# delay_channel.net
KiCad netlist of a schematic drawn in Altium Designer
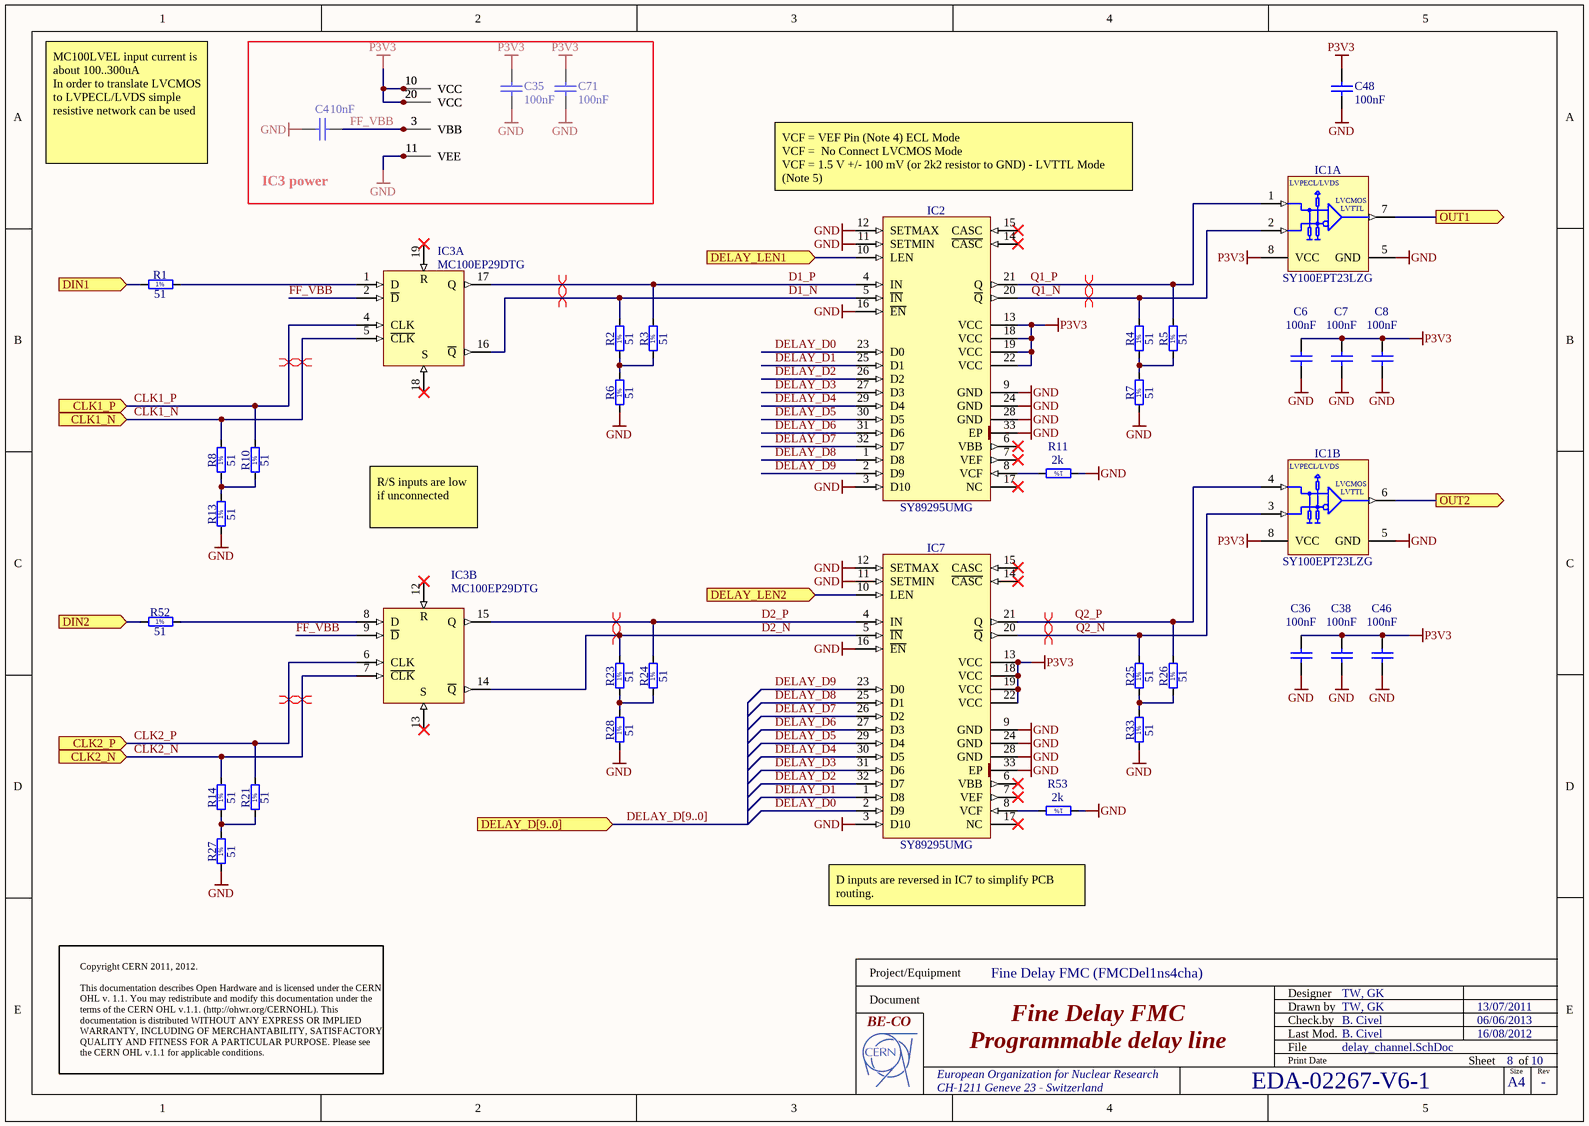
[diagram p0: delay_channel.SchDoc]

(export (version "E")
  (design (tool "Eeschema 10.0.6"))
  (components
    (comp (ref "C4")
      (value "10nF")
      (footprint "CAPC1608X87N")
      (description "Non-polarised capacitor")
      (fields
        (field (name "PART NUMBER") "CC0603_10NF_50V_10%_X7R")
        (field (name "VOLTAGE") "50V")
        (field (name "AUTHOR") "CERN DEM JLC")
      )
      (libsource (lib "Capacitors") (part "Capacitor - non polarized"))
    )
    (comp (ref "C6")
      (value "100nF")
      (footprint "CAPC1608X87N")
      (description "Non-polarised capacitor")
      (fields
        (field (name "MANUFACTURER1 PART NUMBER") "223858615649")
        (field (name "MANUFACTURER") "GENERIC")
        (field (name "AUTHOR") "CERN DEM JLC")
      )
      (libsource (lib "Capacitors") (part "Capacitor - non polarized"))
    )
    (comp (ref "C7")
      (value "100nF")
      (footprint "CAPC1608X87N")
      (description "Non-polarised capacitor")
      (fields
        (field (name "MANUFACTURER1 PART NUMBER") "223858615649")
        (field (name "MANUFACTURER") "GENERIC")
        (field (name "AUTHOR") "CERN DEM JLC")
      )
      (libsource (lib "Capacitors") (part "Capacitor - non polarized"))
    )
    (comp (ref "C8")
      (value "100nF")
      (footprint "CAPC1608X87N")
      (description "Non-polarised capacitor")
      (fields
        (field (name "MANUFACTURER1 PART NUMBER") "223858615649")
        (field (name "MANUFACTURER") "GENERIC")
        (field (name "AUTHOR") "CERN DEM JLC")
      )
      (libsource (lib "Capacitors") (part "Capacitor - non polarized"))
    )
    (comp (ref "C35")
      (value "100nF")
      (footprint "CAPC1608X87N")
      (description "Non-polarised capacitor")
      (fields
        (field (name "MANUFACTURER1 PART NUMBER") "223858615649")
        (field (name "MANUFACTURER") "GENERIC")
        (field (name "AUTHOR") "CERN DEM JLC")
      )
      (libsource (lib "Capacitors") (part "Capacitor - non polarized"))
    )
    (comp (ref "C36")
      (value "100nF")
      (footprint "CAPC1608X87N")
      (description "Non-polarised capacitor")
      (fields
        (field (name "MANUFACTURER1 PART NUMBER") "223858615649")
        (field (name "MANUFACTURER") "GENERIC")
        (field (name "AUTHOR") "CERN DEM JLC")
      )
      (libsource (lib "Capacitors") (part "Capacitor - non polarized"))
    )
    (comp (ref "C38")
      (value "100nF")
      (footprint "CAPC1608X87N")
      (description "Non-polarised capacitor")
      (fields
        (field (name "MANUFACTURER1 PART NUMBER") "223858615649")
        (field (name "MANUFACTURER") "GENERIC")
        (field (name "AUTHOR") "CERN DEM JLC")
      )
      (libsource (lib "Capacitors") (part "Capacitor - non polarized"))
    )
    (comp (ref "C46")
      (value "100nF")
      (footprint "CAPC1608X87N")
      (description "Non-polarised capacitor")
      (fields
        (field (name "MANUFACTURER1 PART NUMBER") "223858615649")
        (field (name "MANUFACTURER") "GENERIC")
        (field (name "AUTHOR") "CERN DEM JLC")
      )
      (libsource (lib "Capacitors") (part "Capacitor - non polarized"))
    )
    (comp (ref "C48")
      (value "100nF")
      (footprint "CAPC1608X87N")
      (description "Non-polarised capacitor")
      (fields
        (field (name "MANUFACTURER1 PART NUMBER") "223858615649")
        (field (name "MANUFACTURER") "GENERIC")
        (field (name "AUTHOR") "CERN DEM JLC")
      )
      (libsource (lib "Capacitors") (part "Capacitor - non polarized"))
    )
    (comp (ref "C71")
      (value "100nF")
      (footprint "CAPC1608X87N")
      (description "Non-polarised capacitor")
      (fields
        (field (name "MANUFACTURER1 PART NUMBER") "223858615649")
        (field (name "MANUFACTURER") "GENERIC")
        (field (name "AUTHOR") "CERN DEM JLC")
      )
      (libsource (lib "Capacitors") (part "Capacitor - non polarized"))
    )
    (comp (ref "IC1")
      (value "SY100EPT23LZG")
      (footprint "SOIC127P600X175-8N")
      (description "3.3V Dual Differential LVPECL/LVDS/CML  to LVTTL/LVCMOS Translator")
      (fields (field (name "MANUFACTURER") "MICREL") (field (name "AUTHOR") "CERN DEM JLC"))
      (libsource (lib "ICs And Semiconductors") (part "100EPT23D_a"))
    )
    (comp (ref "IC2")
      (value "SY89295UMG")
      (footprint "QFN50P500X500X90-33N-S320")
      (description "2.5V/3.3V 1.5GHz Precision LVPECL Programmable Delay")
      (fields (field (name "MANUFACTURER") "MICREL") (field (name "AUTHOR") "CERN DEM JLC"))
      (libsource (lib "ICs And Semiconductors") (part "SY89295UMG"))
    )
    (comp (ref "IC3")
      (value "MC100EP29DTG")
      (footprint "SOP65P640X120-20N")
      (description "3.3V/5V ECL Dual Differential Data and Clock D Flip-Flop With Set and Reset")
      (fields (field (name "MANUFACTURER") "ON SEMICONDUCTOR") (field (name "AUTHOR") "CERN DEM JLC"))
      (libsource (lib "ICs And Semiconductors") (part "100EP29D"))
    )
    (comp (ref "IC7")
      (value "SY89295UMG")
      (footprint "QFN50P500X500X90-33N-S320")
      (description "2.5V/3.3V 1.5GHz Precision LVPECL Programmable Delay")
      (fields (field (name "MANUFACTURER") "MICREL") (field (name "AUTHOR") "CERN DEM JLC"))
      (libsource (lib "ICs And Semiconductors") (part "SY89295UMG"))
    )
    (comp (ref "R1")
      (value "51")
      (footprint "RESC1608X55N")
      (description "Resistor - 1%")
      (fields
        (field (name "PART NUMBER") "R0603_51R_1%_0.1W_100PPM")
        (field (name "POWER") "0.1W")
        (field (name "AUTHOR") "CERN DEM JLC")
      )
      (libsource (lib "Resistors") (part "Resistor - 1%"))
    )
    (comp (ref "R2")
      (value "51")
      (footprint "RESC1608X55N")
      (description "Resistor - 1%")
      (fields
        (field (name "PART NUMBER") "R0603_51R_1%_0.1W_100PPM")
        (field (name "POWER") "0.1W")
        (field (name "AUTHOR") "CERN DEM JLC")
      )
      (libsource (lib "Resistors") (part "Resistor - 1%"))
    )
    (comp (ref "R3")
      (value "51")
      (footprint "RESC1608X55N")
      (description "Resistor - 1%")
      (fields
        (field (name "PART NUMBER") "R0603_51R_1%_0.1W_100PPM")
        (field (name "POWER") "0.1W")
        (field (name "AUTHOR") "CERN DEM JLC")
      )
      (libsource (lib "Resistors") (part "Resistor - 1%"))
    )
    (comp (ref "R4")
      (value "51")
      (footprint "RESC1608X55N")
      (description "Resistor - 1%")
      (fields
        (field (name "PART NUMBER") "R0603_51R_1%_0.1W_100PPM")
        (field (name "POWER") "0.1W")
        (field (name "AUTHOR") "CERN DEM JLC")
      )
      (libsource (lib "Resistors") (part "Resistor - 1%"))
    )
    (comp (ref "R5")
      (value "51")
      (footprint "RESC1608X55N")
      (description "Resistor - 1%")
      (fields
        (field (name "PART NUMBER") "R0603_51R_1%_0.1W_100PPM")
        (field (name "POWER") "0.1W")
        (field (name "AUTHOR") "CERN DEM JLC")
      )
      (libsource (lib "Resistors") (part "Resistor - 1%"))
    )
    (comp (ref "R6")
      (value "51")
      (footprint "RESC1608X55N")
      (description "Resistor - 1%")
      (fields
        (field (name "PART NUMBER") "R0603_51R_1%_0.1W_100PPM")
        (field (name "POWER") "0.1W")
        (field (name "AUTHOR") "CERN DEM JLC")
      )
      (libsource (lib "Resistors") (part "Resistor - 1%"))
    )
    (comp (ref "R7")
      (value "51")
      (footprint "RESC1608X55N")
      (description "Resistor - 1%")
      (fields
        (field (name "PART NUMBER") "R0603_51R_1%_0.1W_100PPM")
        (field (name "POWER") "0.1W")
        (field (name "AUTHOR") "CERN DEM JLC")
      )
      (libsource (lib "Resistors") (part "Resistor - 1%"))
    )
    (comp (ref "R8")
      (value "51")
      (footprint "RESC1608X55N")
      (description "Resistor - 1%")
      (fields
        (field (name "PART NUMBER") "R0603_51R_1%_0.1W_100PPM")
        (field (name "POWER") "0.1W")
        (field (name "AUTHOR") "CERN DEM JLC")
      )
      (libsource (lib "Resistors") (part "Resistor - 1%"))
    )
    (comp (ref "R10")
      (value "51")
      (footprint "RESC1608X55N")
      (description "Resistor - 1%")
      (fields
        (field (name "PART NUMBER") "R0603_51R_1%_0.1W_100PPM")
        (field (name "POWER") "0.1W")
        (field (name "AUTHOR") "CERN DEM JLC")
      )
      (libsource (lib "Resistors") (part "Resistor - 1%"))
    )
    (comp (ref "R11")
      (value "2k")
      (footprint "RESC1608X55N")
      (description "Resistor - 1%")
      (fields
        (field (name "PART NUMBER") "R0603_2K_1%_0.1W_100PPM")
        (field (name "POWER") "0.1W")
        (field (name "AUTHOR") "CERN DEM JLC")
      )
      (libsource (lib "Resistors") (part "Resistor - 1%"))
    )
    (comp (ref "R13")
      (value "51")
      (footprint "RESC1608X55N")
      (description "Resistor - 1%")
      (fields
        (field (name "PART NUMBER") "R0603_51R_1%_0.1W_100PPM")
        (field (name "POWER") "0.1W")
        (field (name "AUTHOR") "CERN DEM JLC")
      )
      (libsource (lib "Resistors") (part "Resistor - 1%"))
    )
    (comp (ref "R14")
      (value "51")
      (footprint "RESC1608X55N")
      (description "Resistor - 1%")
      (fields
        (field (name "PART NUMBER") "R0603_51R_1%_0.1W_100PPM")
        (field (name "POWER") "0.1W")
        (field (name "AUTHOR") "CERN DEM JLC")
      )
      (libsource (lib "Resistors") (part "Resistor - 1%"))
    )
    (comp (ref "R21")
      (value "51")
      (footprint "RESC1608X55N")
      (description "Resistor - 1%")
      (fields
        (field (name "PART NUMBER") "R0603_51R_1%_0.1W_100PPM")
        (field (name "POWER") "0.1W")
        (field (name "AUTHOR") "CERN DEM JLC")
      )
      (libsource (lib "Resistors") (part "Resistor - 1%"))
    )
    (comp (ref "R23")
      (value "51")
      (footprint "RESC1608X55N")
      (description "Resistor - 1%")
      (fields
        (field (name "PART NUMBER") "R0603_51R_1%_0.1W_100PPM")
        (field (name "POWER") "0.1W")
        (field (name "AUTHOR") "CERN DEM JLC")
      )
      (libsource (lib "Resistors") (part "Resistor - 1%"))
    )
    (comp (ref "R24")
      (value "51")
      (footprint "RESC1608X55N")
      (description "Resistor - 1%")
      (fields
        (field (name "PART NUMBER") "R0603_51R_1%_0.1W_100PPM")
        (field (name "POWER") "0.1W")
        (field (name "AUTHOR") "CERN DEM JLC")
      )
      (libsource (lib "Resistors") (part "Resistor - 1%"))
    )
    (comp (ref "R25")
      (value "51")
      (footprint "RESC1608X55N")
      (description "Resistor - 1%")
      (fields
        (field (name "PART NUMBER") "R0603_51R_1%_0.1W_100PPM")
        (field (name "POWER") "0.1W")
        (field (name "AUTHOR") "CERN DEM JLC")
      )
      (libsource (lib "Resistors") (part "Resistor - 1%"))
    )
    (comp (ref "R26")
      (value "51")
      (footprint "RESC1608X55N")
      (description "Resistor - 1%")
      (fields
        (field (name "PART NUMBER") "R0603_51R_1%_0.1W_100PPM")
        (field (name "POWER") "0.1W")
        (field (name "AUTHOR") "CERN DEM JLC")
      )
      (libsource (lib "Resistors") (part "Resistor - 1%"))
    )
    (comp (ref "R27")
      (value "51")
      (footprint "RESC1608X55N")
      (description "Resistor - 1%")
      (fields
        (field (name "PART NUMBER") "R0603_51R_1%_0.1W_100PPM")
        (field (name "POWER") "0.1W")
        (field (name "AUTHOR") "CERN DEM JLC")
      )
      (libsource (lib "Resistors") (part "Resistor - 1%"))
    )
    (comp (ref "R28")
      (value "51")
      (footprint "RESC1608X55N")
      (description "Resistor - 1%")
      (fields
        (field (name "PART NUMBER") "R0603_51R_1%_0.1W_100PPM")
        (field (name "POWER") "0.1W")
        (field (name "AUTHOR") "CERN DEM JLC")
      )
      (libsource (lib "Resistors") (part "Resistor - 1%"))
    )
    (comp (ref "R33")
      (value "51")
      (footprint "RESC1608X55N")
      (description "Resistor - 1%")
      (fields
        (field (name "PART NUMBER") "R0603_51R_1%_0.1W_100PPM")
        (field (name "POWER") "0.1W")
        (field (name "AUTHOR") "CERN DEM JLC")
      )
      (libsource (lib "Resistors") (part "Resistor - 1%"))
    )
    (comp (ref "R52")
      (value "51")
      (footprint "RESC1608X55N")
      (description "Resistor - 1%")
      (fields
        (field (name "PART NUMBER") "R0603_51R_1%_0.1W_100PPM")
        (field (name "POWER") "0.1W")
        (field (name "AUTHOR") "CERN DEM JLC")
      )
      (libsource (lib "Resistors") (part "Resistor - 1%"))
    )
    (comp (ref "R53")
      (value "2k")
      (footprint "RESC1608X55N")
      (description "Resistor - 1%")
      (fields
        (field (name "PART NUMBER") "R0603_2K_1%_0.1W_100PPM")
        (field (name "POWER") "0.1W")
        (field (name "AUTHOR") "CERN DEM JLC")
      )
      (libsource (lib "Resistors") (part "Resistor - 1%"))
    )
  )
  (nets
    (net (code "1") (name "/CLK1_N") (class "Default")
      (node (ref "IC3") (pin "5") (pinfunction "~{CLK}_5") (pintype "input"))
      (node (ref "R8") (pin "2") (pinfunction "2_2") (pintype "passive"))
    )
    (net (code "2") (name "/CLK1_P") (class "Default")
      (node (ref "IC3") (pin "4") (pinfunction "CLK_4") (pintype "input"))
      (node (ref "R10") (pin "2") (pinfunction "2_2") (pintype "passive"))
    )
    (net (code "3") (name "/CLK2_N") (class "Default")
      (node (ref "IC3") (pin "7") (pinfunction "~{CLK}_7") (pintype "input"))
      (node (ref "R14") (pin "2") (pinfunction "2_2") (pintype "passive"))
    )
    (net (code "4") (name "/CLK2_P") (class "Default")
      (node (ref "IC3") (pin "6") (pinfunction "CLK_6") (pintype "input"))
      (node (ref "R21") (pin "2") (pinfunction "2_2") (pintype "passive"))
    )
    (net (code "5") (name "/D1_N") (class "Default")
      (node (ref "IC2") (pin "5") (pinfunction "~{IN}_5") (pintype "input"))
      (node (ref "IC3") (pin "16") (pinfunction "~{Q}_16") (pintype "output"))
      (node (ref "R2") (pin "2") (pinfunction "2_2") (pintype "passive"))
    )
    (net (code "6") (name "/D1_P") (class "Default")
      (node (ref "IC2") (pin "4") (pinfunction "IN_4") (pintype "input"))
      (node (ref "IC3") (pin "17") (pinfunction "Q_17") (pintype "output"))
      (node (ref "R3") (pin "2") (pinfunction "2_2") (pintype "passive"))
    )
    (net (code "7") (name "/D2_N") (class "Default")
      (node (ref "IC3") (pin "14") (pinfunction "~{Q}_14") (pintype "output"))
      (node (ref "IC7") (pin "5") (pinfunction "~{IN}_5") (pintype "input"))
      (node (ref "R23") (pin "2") (pinfunction "2_2") (pintype "passive"))
    )
    (net (code "8") (name "/D2_P") (class "Default")
      (node (ref "IC3") (pin "15") (pinfunction "Q_15") (pintype "output"))
      (node (ref "IC7") (pin "4") (pinfunction "IN_4") (pintype "input"))
      (node (ref "R24") (pin "2") (pinfunction "2_2") (pintype "passive"))
    )
    (net (code "9") (name "/DELAY_D0") (class "Default")
      (node (ref "IC2") (pin "23") (pinfunction "D0_23") (pintype "input"))
      (node (ref "IC7") (pin "2") (pinfunction "D9_2") (pintype "input"))
    )
    (net (code "10") (name "/DELAY_D1") (class "Default")
      (node (ref "IC2") (pin "25") (pinfunction "D1_25") (pintype "input"))
      (node (ref "IC7") (pin "1") (pinfunction "D8_1") (pintype "input"))
    )
    (net (code "11") (name "/DELAY_D2") (class "Default")
      (node (ref "IC2") (pin "26") (pinfunction "D2_26") (pintype "input"))
      (node (ref "IC7") (pin "32") (pinfunction "D7_32") (pintype "input"))
    )
    (net (code "12") (name "/DELAY_D3") (class "Default")
      (node (ref "IC2") (pin "27") (pinfunction "D3_27") (pintype "input"))
      (node (ref "IC7") (pin "31") (pinfunction "D6_31") (pintype "input"))
    )
    (net (code "13") (name "/DELAY_D4") (class "Default")
      (node (ref "IC2") (pin "29") (pinfunction "D4_29") (pintype "input"))
      (node (ref "IC7") (pin "30") (pinfunction "D5_30") (pintype "input"))
    )
    (net (code "14") (name "/DELAY_D5") (class "Default")
      (node (ref "IC2") (pin "30") (pinfunction "D5_30") (pintype "input"))
      (node (ref "IC7") (pin "29") (pinfunction "D4_29") (pintype "input"))
    )
    (net (code "15") (name "/DELAY_D6") (class "Default")
      (node (ref "IC2") (pin "31") (pinfunction "D6_31") (pintype "input"))
      (node (ref "IC7") (pin "27") (pinfunction "D3_27") (pintype "input"))
    )
    (net (code "16") (name "/DELAY_D7") (class "Default")
      (node (ref "IC2") (pin "32") (pinfunction "D7_32") (pintype "input"))
      (node (ref "IC7") (pin "26") (pinfunction "D2_26") (pintype "input"))
    )
    (net (code "17") (name "/DELAY_D8") (class "Default")
      (node (ref "IC2") (pin "1") (pinfunction "D8_1") (pintype "input"))
      (node (ref "IC7") (pin "25") (pinfunction "D1_25") (pintype "input"))
    )
    (net (code "18") (name "/DELAY_D9") (class "Default")
      (node (ref "IC2") (pin "2") (pinfunction "D9_2") (pintype "input"))
      (node (ref "IC7") (pin "23") (pinfunction "D0_23") (pintype "input"))
    )
    (net (code "20") (name "/DELAY_LEN1") (class "Default")
      (node (ref "IC2") (pin "10") (pinfunction "LEN_10") (pintype "input"))
    )
    (net (code "21") (name "/DELAY_LEN2") (class "Default")
      (node (ref "IC7") (pin "10") (pinfunction "LEN_10") (pintype "input"))
    )
    (net (code "22") (name "/DIN1") (class "Default")
      (node (ref "R1") (pin "2") (pinfunction "2_2") (pintype "passive"))
    )
    (net (code "23") (name "/DIN2") (class "Default")
      (node (ref "R52") (pin "2") (pinfunction "2_2") (pintype "passive"))
    )
    (net (code "24") (name "/FF_VBB") (class "Default")
      (node (ref "C4") (pin "1") (pinfunction "1_1") (pintype "passive"))
      (node (ref "IC3") (pin "2") (pinfunction "~{D}_2") (pintype "input"))
      (node (ref "IC3") (pin "3") (pinfunction "VBB_3") (pintype "power_in"))
      (node (ref "IC3") (pin "9") (pinfunction "~{D}_9") (pintype "input"))
    )
    (net (code "25") (name "/OUT1") (class "Default")
      (node (ref "IC1") (pin "7") (pinfunction "Q0_7") (pintype "output"))
    )
    (net (code "26") (name "/OUT2") (class "Default")
      (node (ref "IC1") (pin "6") (pinfunction "Q0_6") (pintype "output"))
    )
    (net (code "27") (name "/Q1_N") (class "Default")
      (node (ref "IC1") (pin "2") (pinfunction "~{D0}_2") (pintype "input"))
      (node (ref "IC2") (pin "20") (pinfunction "~{Q}_20") (pintype "output"))
      (node (ref "R4") (pin "2") (pinfunction "2_2") (pintype "passive"))
    )
    (net (code "28") (name "/Q1_P") (class "Default")
      (node (ref "IC1") (pin "1") (pinfunction "D0_1") (pintype "input"))
      (node (ref "IC2") (pin "21") (pinfunction "Q_21") (pintype "output"))
      (node (ref "R5") (pin "2") (pinfunction "2_2") (pintype "passive"))
    )
    (net (code "29") (name "/Q2_N") (class "Default")
      (node (ref "IC1") (pin "3") (pinfunction "~{D0}_3") (pintype "input"))
      (node (ref "IC7") (pin "20") (pinfunction "~{Q}_20") (pintype "output"))
      (node (ref "R25") (pin "2") (pinfunction "2_2") (pintype "passive"))
    )
    (net (code "30") (name "/Q2_P") (class "Default")
      (node (ref "IC1") (pin "4") (pinfunction "D0_4") (pintype "input"))
      (node (ref "IC7") (pin "21") (pinfunction "Q_21") (pintype "output"))
      (node (ref "R26") (pin "2") (pinfunction "2_2") (pintype "passive"))
    )
    (net (code "31") (name "GND") (class "Default")
      (node (ref "C35") (pin "1") (pinfunction "1_1") (pintype "passive"))
      (node (ref "C36") (pin "2") (pinfunction "2_2") (pintype "passive"))
      (node (ref "C38") (pin "2") (pinfunction "2_2") (pintype "passive"))
      (node (ref "C4") (pin "2") (pinfunction "2_2") (pintype "passive"))
      (node (ref "C46") (pin "2") (pinfunction "2_2") (pintype "passive"))
      (node (ref "C48") (pin "2") (pinfunction "2_2") (pintype "passive"))
      (node (ref "C6") (pin "2") (pinfunction "2_2") (pintype "passive"))
      (node (ref "C7") (pin "2") (pinfunction "2_2") (pintype "passive"))
      (node (ref "C71") (pin "1") (pinfunction "1_1") (pintype "passive"))
      (node (ref "C8") (pin "2") (pinfunction "2_2") (pintype "passive"))
      (node (ref "IC1") (pin "5") (pinfunction "GND_5") (pintype "power_in"))
      (node (ref "IC2") (pin "11") (pinfunction "SETMIN_11") (pintype "input"))
      (node (ref "IC2") (pin "12") (pinfunction "SETMAX_12") (pintype "input"))
      (node (ref "IC2") (pin "16") (pinfunction "~{EN}_16") (pintype "input"))
      (node (ref "IC2") (pin "24") (pinfunction "GND_24") (pintype "power_in"))
      (node (ref "IC2") (pin "28") (pinfunction "GND_28") (pintype "power_in"))
      (node (ref "IC2") (pin "3") (pinfunction "D10_3") (pintype "input"))
      (node (ref "IC2") (pin "33") (pinfunction "EP_33") (pintype "power_in"))
      (node (ref "IC2") (pin "9") (pinfunction "GND_9") (pintype "power_in"))
      (node (ref "IC3") (pin "11") (pinfunction "VEE_11") (pintype "power_in"))
      (node (ref "IC7") (pin "11") (pinfunction "SETMIN_11") (pintype "input"))
      (node (ref "IC7") (pin "12") (pinfunction "SETMAX_12") (pintype "input"))
      (node (ref "IC7") (pin "16") (pinfunction "~{EN}_16") (pintype "input"))
      (node (ref "IC7") (pin "24") (pinfunction "GND_24") (pintype "power_in"))
      (node (ref "IC7") (pin "28") (pinfunction "GND_28") (pintype "power_in"))
      (node (ref "IC7") (pin "3") (pinfunction "D10_3") (pintype "input"))
      (node (ref "IC7") (pin "33") (pinfunction "EP_33") (pintype "power_in"))
      (node (ref "IC7") (pin "9") (pinfunction "GND_9") (pintype "power_in"))
      (node (ref "R11") (pin "1") (pinfunction "1_1") (pintype "passive"))
      (node (ref "R13") (pin "1") (pinfunction "1_1") (pintype "passive"))
      (node (ref "R27") (pin "1") (pinfunction "1_1") (pintype "passive"))
      (node (ref "R28") (pin "1") (pinfunction "1_1") (pintype "passive"))
      (node (ref "R33") (pin "1") (pinfunction "1_1") (pintype "passive"))
      (node (ref "R53") (pin "1") (pinfunction "1_1") (pintype "passive"))
      (node (ref "R6") (pin "1") (pinfunction "1_1") (pintype "passive"))
      (node (ref "R7") (pin "1") (pinfunction "1_1") (pintype "passive"))
    )
    (net (code "32") (name "Net-(IC2-VCF)") (class "Default")
      (node (ref "IC2") (pin "8") (pinfunction "VCF_8") (pintype "input"))
      (node (ref "R11") (pin "2") (pinfunction "2_2") (pintype "passive"))
    )
    (net (code "33") (name "Net-(IC3A-D)") (class "Default")
      (node (ref "IC3") (pin "1") (pinfunction "D_1") (pintype "input"))
      (node (ref "R1") (pin "1") (pinfunction "1_1") (pintype "passive"))
    )
    (net (code "34") (name "Net-(IC3B-D)") (class "Default")
      (node (ref "IC3") (pin "8") (pinfunction "D_8") (pintype "input"))
      (node (ref "R52") (pin "1") (pinfunction "1_1") (pintype "passive"))
    )
    (net (code "35") (name "Net-(IC7-VCF)") (class "Default")
      (node (ref "IC7") (pin "8") (pinfunction "VCF_8") (pintype "input"))
      (node (ref "R53") (pin "2") (pinfunction "2_2") (pintype "passive"))
    )
    (net (code "36") (name "Net-(R2-Pad1)") (class "Default")
      (node (ref "R2") (pin "1") (pinfunction "1_1") (pintype "passive"))
      (node (ref "R3") (pin "1") (pinfunction "1_1") (pintype "passive"))
      (node (ref "R6") (pin "2") (pinfunction "2_2") (pintype "passive"))
    )
    (net (code "37") (name "Net-(R4-Pad1)") (class "Default")
      (node (ref "R4") (pin "1") (pinfunction "1_1") (pintype "passive"))
      (node (ref "R5") (pin "1") (pinfunction "1_1") (pintype "passive"))
      (node (ref "R7") (pin "2") (pinfunction "2_2") (pintype "passive"))
    )
    (net (code "38") (name "Net-(R10-Pad1)") (class "Default")
      (node (ref "R10") (pin "1") (pinfunction "1_1") (pintype "passive"))
      (node (ref "R13") (pin "2") (pinfunction "2_2") (pintype "passive"))
      (node (ref "R8") (pin "1") (pinfunction "1_1") (pintype "passive"))
    )
    (net (code "39") (name "Net-(R14-Pad1)") (class "Default")
      (node (ref "R14") (pin "1") (pinfunction "1_1") (pintype "passive"))
      (node (ref "R21") (pin "1") (pinfunction "1_1") (pintype "passive"))
      (node (ref "R27") (pin "2") (pinfunction "2_2") (pintype "passive"))
    )
    (net (code "40") (name "Net-(R23-Pad1)") (class "Default")
      (node (ref "R23") (pin "1") (pinfunction "1_1") (pintype "passive"))
      (node (ref "R24") (pin "1") (pinfunction "1_1") (pintype "passive"))
      (node (ref "R28") (pin "2") (pinfunction "2_2") (pintype "passive"))
    )
    (net (code "41") (name "Net-(R25-Pad1)") (class "Default")
      (node (ref "R25") (pin "1") (pinfunction "1_1") (pintype "passive"))
      (node (ref "R26") (pin "1") (pinfunction "1_1") (pintype "passive"))
      (node (ref "R33") (pin "2") (pinfunction "2_2") (pintype "passive"))
    )
    (net (code "42") (name "P3V3") (class "Default")
      (node (ref "C35") (pin "2") (pinfunction "2_2") (pintype "passive"))
      (node (ref "C36") (pin "1") (pinfunction "1_1") (pintype "passive"))
      (node (ref "C38") (pin "1") (pinfunction "1_1") (pintype "passive"))
      (node (ref "C46") (pin "1") (pinfunction "1_1") (pintype "passive"))
      (node (ref "C48") (pin "1") (pinfunction "1_1") (pintype "passive"))
      (node (ref "C6") (pin "1") (pinfunction "1_1") (pintype "passive"))
      (node (ref "C7") (pin "1") (pinfunction "1_1") (pintype "passive"))
      (node (ref "C71") (pin "2") (pinfunction "2_2") (pintype "passive"))
      (node (ref "C8") (pin "1") (pinfunction "1_1") (pintype "passive"))
      (node (ref "IC1") (pin "8") (pinfunction "VCC_8") (pintype "power_in"))
      (node (ref "IC2") (pin "13") (pinfunction "VCC_13") (pintype "power_in"))
      (node (ref "IC2") (pin "18") (pinfunction "VCC_18") (pintype "power_in"))
      (node (ref "IC2") (pin "19") (pinfunction "VCC_19") (pintype "power_in"))
      (node (ref "IC2") (pin "22") (pinfunction "VCC_22") (pintype "power_in"))
      (node (ref "IC3") (pin "10") (pinfunction "VCC_10") (pintype "power_in"))
      (node (ref "IC3") (pin "20") (pinfunction "VCC_20") (pintype "power_in"))
      (node (ref "IC7") (pin "13") (pinfunction "VCC_13") (pintype "power_in"))
      (node (ref "IC7") (pin "18") (pinfunction "VCC_18") (pintype "power_in"))
      (node (ref "IC7") (pin "19") (pinfunction "VCC_19") (pintype "power_in"))
      (node (ref "IC7") (pin "22") (pinfunction "VCC_22") (pintype "power_in"))
    )
    (net (code "43") (name "unconnected-(IC2-CASC-Pad15)") (class "Default")
      (node (ref "IC2") (pin "15") (pinfunction "CASC_15") (pintype "input+no_connect"))
    )
    (net (code "44") (name "unconnected-(IC2-NC-Pad17)") (class "Default")
      (node (ref "IC2") (pin "17") (pinfunction "NC_17") (pintype "passive+no_connect"))
    )
    (net (code "45") (name "unconnected-(IC2-VBB-Pad6)") (class "Default")
      (node (ref "IC2") (pin "6") (pinfunction "VBB_6") (pintype "output+no_connect"))
    )
    (net (code "46") (name "unconnected-(IC2-VEF-Pad7)") (class "Default")
      (node (ref "IC2") (pin "7") (pinfunction "VEF_7") (pintype "output+no_connect"))
    )
    (net (code "47") (name "unconnected-(IC2-~{CASC}-Pad14)") (class "Default")
      (node (ref "IC2") (pin "14") (pinfunction "~{CASC}_14") (pintype "input+no_connect"))
    )
    (net (code "48") (name "unconnected-(IC3A-R-Pad19)") (class "Default")
      (node (ref "IC3") (pin "19") (pinfunction "R_19") (pintype "input+no_connect"))
    )
    (net (code "49") (name "unconnected-(IC3A-S-Pad18)") (class "Default")
      (node (ref "IC3") (pin "18") (pinfunction "S_18") (pintype "input+no_connect"))
    )
    (net (code "50") (name "unconnected-(IC3B-R-Pad12)") (class "Default")
      (node (ref "IC3") (pin "12") (pinfunction "R_12") (pintype "input+no_connect"))
    )
    (net (code "51") (name "unconnected-(IC3B-S-Pad13)") (class "Default")
      (node (ref "IC3") (pin "13") (pinfunction "S_13") (pintype "input+no_connect"))
    )
    (net (code "52") (name "unconnected-(IC7-CASC-Pad15)") (class "Default")
      (node (ref "IC7") (pin "15") (pinfunction "CASC_15") (pintype "input+no_connect"))
    )
    (net (code "53") (name "unconnected-(IC7-NC-Pad17)") (class "Default")
      (node (ref "IC7") (pin "17") (pinfunction "NC_17") (pintype "passive+no_connect"))
    )
    (net (code "54") (name "unconnected-(IC7-VBB-Pad6)") (class "Default")
      (node (ref "IC7") (pin "6") (pinfunction "VBB_6") (pintype "output+no_connect"))
    )
    (net (code "55") (name "unconnected-(IC7-VEF-Pad7)") (class "Default")
      (node (ref "IC7") (pin "7") (pinfunction "VEF_7") (pintype "output+no_connect"))
    )
    (net (code "56") (name "unconnected-(IC7-~{CASC}-Pad14)") (class "Default")
      (node (ref "IC7") (pin "14") (pinfunction "~{CASC}_14") (pintype "input+no_connect"))
    )
  )
)
